# EEPROM.net
KiCad netlist of a schematic drawn in Altium Designer
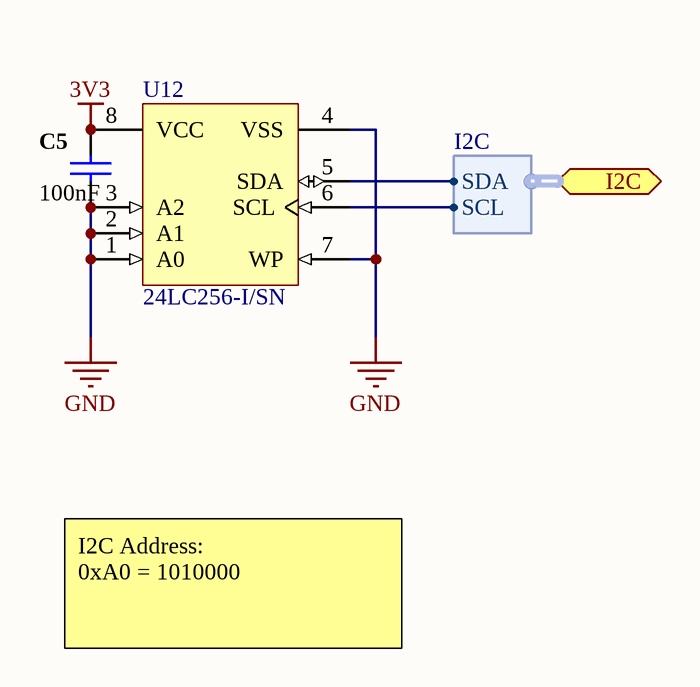
[diagram p0: EEPROM.SchDoc]

(export (version "E")
  (design (tool "Eeschema 10.0.6"))
  (components
    (comp (ref "C5")
      (value "100nF")
      (footprint "0805C-GENERIC")
      (description "Capacitor, Ceramic, 10% 10V 0805 X7R")
      (fields (field (name "CAPACITANCE") "100nF") (field (name "TOLERANCE") "10 %"))
      (libsource (lib "altium-import") (part "root_0_CAP-NP_"))
    )
    (comp (ref "U12")
      (value "24LC256-I/SN")
      (footprint "SOIC-SN8_L")
      (description "256Kbit, 400kHz, 2.5V, I2C Serial EEPROM, 8-Pin SOIC 150mil, Industrial Temperature")
      (fields (field (name "MANUFACTURER") "Microchip"))
      (libsource (lib "Microchip I2C Serial EEPROM") (part "24LC256-I/SN"))
    )
  )
  (nets
    (net (code "2") (name "/SCL") (class "Default")
      (node (ref "U12") (pin "6") (pinfunction "SCL_6") (pintype "input"))
    )
    (net (code "3") (name "/SDA") (class "Default")
      (node (ref "U12") (pin "5") (pinfunction "SDA_5") (pintype "bidirectional"))
    )
    (net (code "5") (name "3V3") (class "Default")
      (node (ref "C5") (pin "1") (pinfunction "1_1") (pintype "passive"))
      (node (ref "U12") (pin "8") (pinfunction "VCC_8") (pintype "power_in"))
    )
    (net (code "6") (name "GND") (class "Default")
      (node (ref "C5") (pin "2") (pinfunction "2_2") (pintype "passive"))
      (node (ref "U12") (pin "1") (pinfunction "A0_1") (pintype "input"))
      (node (ref "U12") (pin "2") (pinfunction "A1_2") (pintype "input"))
      (node (ref "U12") (pin "3") (pinfunction "A2_3") (pintype "input"))
      (node (ref "U12") (pin "4") (pinfunction "VSS_4") (pintype "power_in"))
      (node (ref "U12") (pin "7") (pinfunction "WP_7") (pintype "input"))
    )
  )
)
